# videopac_cart.net
KiCad netlist of a schematic drawn in EAGLE
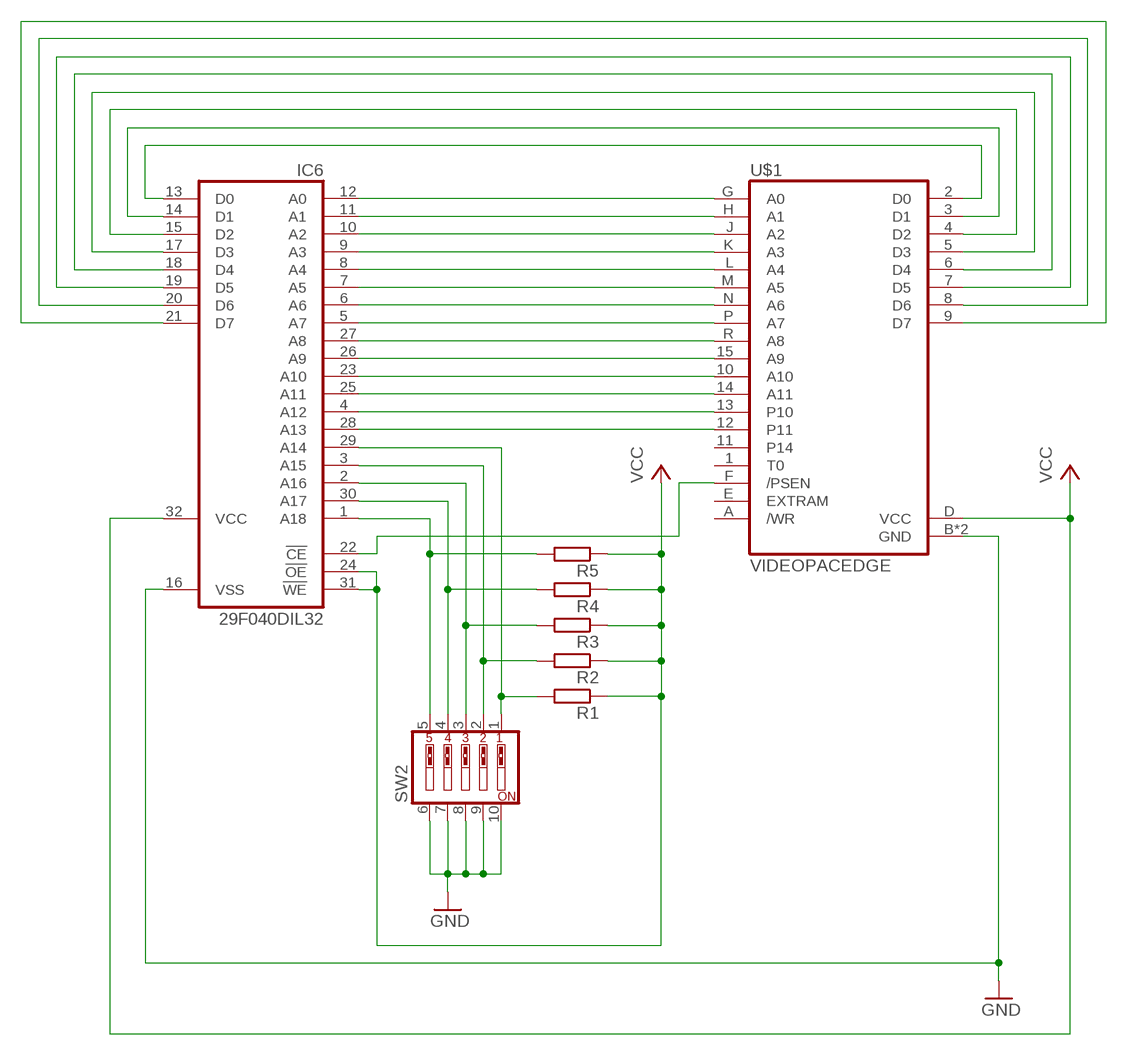
[diagram p0: schematic, sheet 1]

(export (version "E")
  (design (tool "Eeschema 10.0.6"))
  (components
    (comp (ref "IC6")
      (value "29F040DIL32")
      (footprint "eagle-import:DIL32")
      (libsource (lib "eagle-import") (part "29F040DIL32"))
    )
    (comp (ref "R1")
      (value "R-EU_0207/10")
      (footprint "eagle-import:0207_10")
      (libsource (lib "eagle-import") (part "R-EU_0207/10"))
    )
    (comp (ref "R2")
      (value "R-EU_0207/10")
      (footprint "eagle-import:0207_10")
      (libsource (lib "eagle-import") (part "R-EU_0207/10"))
    )
    (comp (ref "R3")
      (value "R-EU_0207/10")
      (footprint "eagle-import:0207_10")
      (libsource (lib "eagle-import") (part "R-EU_0207/10"))
    )
    (comp (ref "R4")
      (value "R-EU_0207/10")
      (footprint "eagle-import:0207_10")
      (libsource (lib "eagle-import") (part "R-EU_0207/10"))
    )
    (comp (ref "R5")
      (value "R-EU_0207/10")
      (footprint "eagle-import:0207_10")
      (libsource (lib "eagle-import") (part "R-EU_0207/10"))
    )
    (comp (ref "SW2")
      (value "SW_DIP-5")
      (footprint "eagle-import:EDG-05")
      (libsource (lib "eagle-import") (part "SW_DIP-5"))
    )
    (comp (ref "U$1")
      (value "VIDEOPACEDGE")
      (footprint "eagle-import:VIDEOPAC")
      (libsource (lib "eagle-import") (part "VIDEOPACEDGE"))
    )
  )
  (nets
    (net (code "1") (name "GND") (class "Default")
      (node (ref "IC6") (pin "16") (pinfunction "VSS_16") (pintype "power_in"))
      (node (ref "SW2") (pin "10") (pinfunction "10_10") (pintype "passive"))
      (node (ref "SW2") (pin "6") (pinfunction "6_6") (pintype "passive"))
      (node (ref "SW2") (pin "7") (pinfunction "7_7") (pintype "passive"))
      (node (ref "SW2") (pin "8") (pinfunction "8_8") (pintype "passive"))
      (node (ref "SW2") (pin "9") (pinfunction "9_9") (pintype "passive"))
      (node (ref "U$1") (pin "B") (pinfunction "GND_B") (pintype "power_in"))
      (node (ref "U$1") (pin "C") (pinfunction "GND_C") (pintype "power_in"))
    )
    (net (code "2") (name "Net-(IC6-A0)") (class "Default")
      (node (ref "IC6") (pin "12") (pinfunction "A0_12") (pintype "input"))
      (node (ref "U$1") (pin "G") (pinfunction "A0_G") (pintype "output"))
    )
    (net (code "3") (name "Net-(IC6-A1)") (class "Default")
      (node (ref "IC6") (pin "11") (pinfunction "A1_11") (pintype "input"))
      (node (ref "U$1") (pin "H") (pinfunction "A1_H") (pintype "output"))
    )
    (net (code "4") (name "Net-(IC6-A2)") (class "Default")
      (node (ref "IC6") (pin "10") (pinfunction "A2_10") (pintype "input"))
      (node (ref "U$1") (pin "J") (pinfunction "A2_J") (pintype "output"))
    )
    (net (code "5") (name "Net-(IC6-A3)") (class "Default")
      (node (ref "IC6") (pin "9") (pinfunction "A3_9") (pintype "input"))
      (node (ref "U$1") (pin "K") (pinfunction "A3_K") (pintype "output"))
    )
    (net (code "6") (name "Net-(IC6-A4)") (class "Default")
      (node (ref "IC6") (pin "8") (pinfunction "A4_8") (pintype "input"))
      (node (ref "U$1") (pin "L") (pinfunction "A4_L") (pintype "output"))
    )
    (net (code "7") (name "Net-(IC6-A5)") (class "Default")
      (node (ref "IC6") (pin "7") (pinfunction "A5_7") (pintype "input"))
      (node (ref "U$1") (pin "M") (pinfunction "A5_M") (pintype "output"))
    )
    (net (code "8") (name "Net-(IC6-A6)") (class "Default")
      (node (ref "IC6") (pin "6") (pinfunction "A6_6") (pintype "input"))
      (node (ref "U$1") (pin "N") (pinfunction "A6_N") (pintype "output"))
    )
    (net (code "9") (name "Net-(IC6-A7)") (class "Default")
      (node (ref "IC6") (pin "5") (pinfunction "A7_5") (pintype "input"))
      (node (ref "U$1") (pin "P") (pinfunction "A7_P") (pintype "output"))
    )
    (net (code "10") (name "Net-(IC6-A8)") (class "Default")
      (node (ref "IC6") (pin "27") (pinfunction "A8_27") (pintype "input"))
      (node (ref "U$1") (pin "R") (pinfunction "A8_R") (pintype "output"))
    )
    (net (code "11") (name "Net-(IC6-A9)") (class "Default")
      (node (ref "IC6") (pin "26") (pinfunction "A9_26") (pintype "input"))
      (node (ref "U$1") (pin "15") (pinfunction "A9_15") (pintype "output"))
    )
    (net (code "12") (name "Net-(IC6-A10)") (class "Default")
      (node (ref "IC6") (pin "23") (pinfunction "A10_23") (pintype "input"))
      (node (ref "U$1") (pin "10") (pinfunction "A10_10") (pintype "output"))
    )
    (net (code "13") (name "Net-(IC6-A11)") (class "Default")
      (node (ref "IC6") (pin "25") (pinfunction "A11_25") (pintype "input"))
      (node (ref "U$1") (pin "14") (pinfunction "A11_14") (pintype "output"))
    )
    (net (code "14") (name "Net-(IC6-A12)") (class "Default")
      (node (ref "IC6") (pin "4") (pinfunction "A12_4") (pintype "input"))
      (node (ref "U$1") (pin "13") (pinfunction "P10_13") (pintype "output"))
    )
    (net (code "15") (name "Net-(IC6-A13)") (class "Default")
      (node (ref "IC6") (pin "28") (pinfunction "A13_28") (pintype "input"))
      (node (ref "U$1") (pin "12") (pinfunction "P11_12") (pintype "output"))
    )
    (net (code "16") (name "Net-(IC6-A14)") (class "Default")
      (node (ref "IC6") (pin "29") (pinfunction "A14_29") (pintype "input"))
      (node (ref "R1") (pin "2") (pinfunction "2_2") (pintype "passive"))
      (node (ref "SW2") (pin "1") (pinfunction "1_1") (pintype "passive"))
    )
    (net (code "17") (name "Net-(IC6-A15)") (class "Default")
      (node (ref "IC6") (pin "3") (pinfunction "A15_3") (pintype "input"))
      (node (ref "R2") (pin "2") (pinfunction "2_2") (pintype "passive"))
      (node (ref "SW2") (pin "2") (pinfunction "2_2") (pintype "passive"))
    )
    (net (code "18") (name "Net-(IC6-A16)") (class "Default")
      (node (ref "IC6") (pin "2") (pinfunction "A16_2") (pintype "input"))
      (node (ref "R3") (pin "2") (pinfunction "2_2") (pintype "passive"))
      (node (ref "SW2") (pin "3") (pinfunction "3_3") (pintype "passive"))
    )
    (net (code "19") (name "Net-(IC6-A17)") (class "Default")
      (node (ref "IC6") (pin "30") (pinfunction "A17_30") (pintype "input"))
      (node (ref "R4") (pin "2") (pinfunction "2_2") (pintype "passive"))
      (node (ref "SW2") (pin "4") (pinfunction "4_4") (pintype "passive"))
    )
    (net (code "20") (name "Net-(IC6-A18)") (class "Default")
      (node (ref "IC6") (pin "1") (pinfunction "A18_1") (pintype "input"))
      (node (ref "R5") (pin "2") (pinfunction "2_2") (pintype "passive"))
      (node (ref "SW2") (pin "5") (pinfunction "5_5") (pintype "passive"))
    )
    (net (code "21") (name "Net-(IC6-D0)") (class "Default")
      (node (ref "IC6") (pin "13") (pinfunction "D0_13") (pintype "tri_state"))
      (node (ref "U$1") (pin "2") (pinfunction "D0_2") (pintype "bidirectional"))
    )
    (net (code "22") (name "Net-(IC6-D1)") (class "Default")
      (node (ref "IC6") (pin "14") (pinfunction "D1_14") (pintype "tri_state"))
      (node (ref "U$1") (pin "3") (pinfunction "D1_3") (pintype "bidirectional"))
    )
    (net (code "23") (name "Net-(IC6-D2)") (class "Default")
      (node (ref "IC6") (pin "15") (pinfunction "D2_15") (pintype "tri_state"))
      (node (ref "U$1") (pin "4") (pinfunction "D2_4") (pintype "bidirectional"))
    )
    (net (code "24") (name "Net-(IC6-D3)") (class "Default")
      (node (ref "IC6") (pin "17") (pinfunction "D3_17") (pintype "tri_state"))
      (node (ref "U$1") (pin "5") (pinfunction "D3_5") (pintype "bidirectional"))
    )
    (net (code "25") (name "Net-(IC6-D4)") (class "Default")
      (node (ref "IC6") (pin "18") (pinfunction "D4_18") (pintype "tri_state"))
      (node (ref "U$1") (pin "6") (pinfunction "D4_6") (pintype "bidirectional"))
    )
    (net (code "26") (name "Net-(IC6-D5)") (class "Default")
      (node (ref "IC6") (pin "19") (pinfunction "D5_19") (pintype "tri_state"))
      (node (ref "U$1") (pin "7") (pinfunction "D5_7") (pintype "bidirectional"))
    )
    (net (code "27") (name "Net-(IC6-D6)") (class "Default")
      (node (ref "IC6") (pin "20") (pinfunction "D6_20") (pintype "tri_state"))
      (node (ref "U$1") (pin "8") (pinfunction "D6_8") (pintype "bidirectional"))
    )
    (net (code "28") (name "Net-(IC6-D7)") (class "Default")
      (node (ref "IC6") (pin "21") (pinfunction "D7_21") (pintype "tri_state"))
      (node (ref "U$1") (pin "9") (pinfunction "D7_9") (pintype "bidirectional"))
    )
    (net (code "29") (name "Net-(IC6-~{CE})") (class "Default")
      (node (ref "IC6") (pin "22") (pinfunction "~{CE}_22") (pintype "input"))
      (node (ref "U$1") (pin "F") (pinfunction "/PSEN_F") (pintype "output"))
    )
    (net (code "30") (name "VCC") (class "Default")
      (node (ref "IC6") (pin "24") (pinfunction "~{OE}_24") (pintype "input"))
      (node (ref "IC6") (pin "31") (pinfunction "~{WE}_31") (pintype "input"))
      (node (ref "IC6") (pin "32") (pinfunction "VCC_32") (pintype "power_in"))
      (node (ref "R1") (pin "1") (pinfunction "1_1") (pintype "passive"))
      (node (ref "R2") (pin "1") (pinfunction "1_1") (pintype "passive"))
      (node (ref "R3") (pin "1") (pinfunction "1_1") (pintype "passive"))
      (node (ref "R4") (pin "1") (pinfunction "1_1") (pintype "passive"))
      (node (ref "R5") (pin "1") (pinfunction "1_1") (pintype "passive"))
      (node (ref "U$1") (pin "D") (pinfunction "VCC_D") (pintype "power_in"))
    )
    (net (code "31") (name "unconnected-(U$1-EXTRAM-PadE)") (class "Default")
      (node (ref "U$1") (pin "E") (pinfunction "EXTRAM_E") (pintype "output"))
    )
    (net (code "32") (name "unconnected-(U$1-P14-Pad11)") (class "Default")
      (node (ref "U$1") (pin "11") (pinfunction "P14_11") (pintype "output"))
    )
    (net (code "33") (name "unconnected-(U$1-T0-Pad1)") (class "Default")
      (node (ref "U$1") (pin "1") (pinfunction "T0_1") (pintype "output"))
    )
    (net (code "34") (name "unconnected-(U$1-{slash}WR-PadA)") (class "Default")
      (node (ref "U$1") (pin "A") (pinfunction "/WR_A") (pintype "output"))
    )
  )
)
